# deska.net
KiCad netlist of a schematic drawn in EAGLE
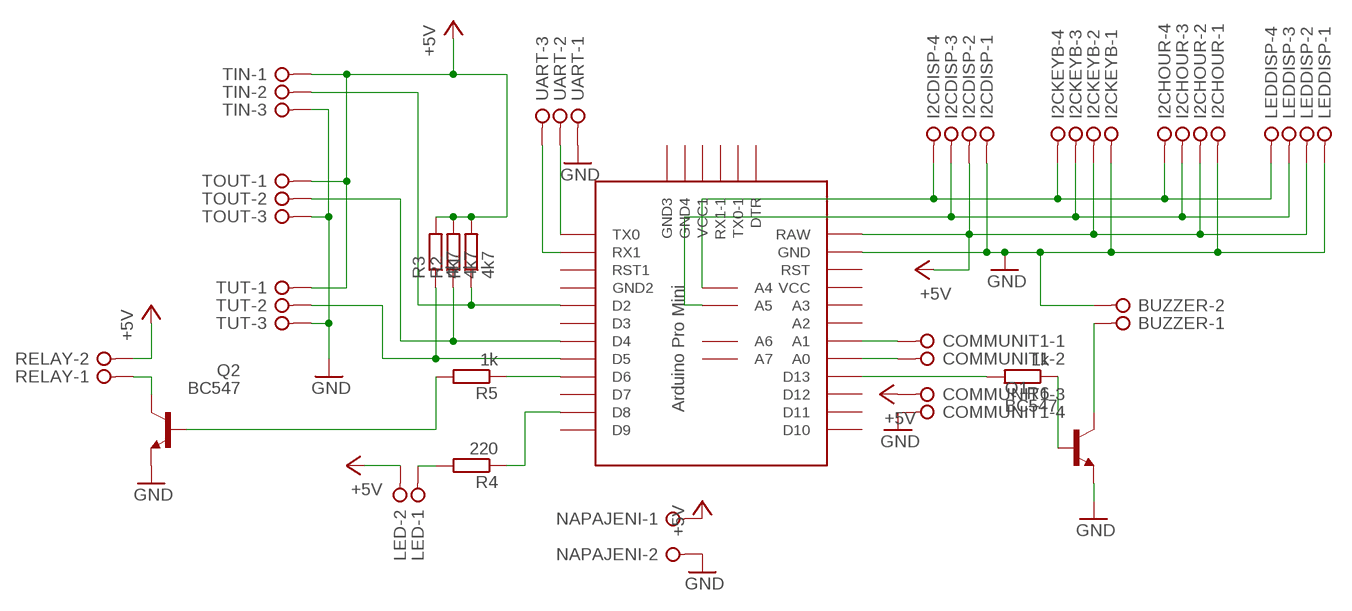
[diagram p0: schematic, sheet 1]

(export (version "E")
  (design (tool "Eeschema 10.0.6"))
  (components
    (comp (ref "BUZZER")
      (value "W237-02P")
      (footprint "eagle-import:W237-132")
      (libsource (lib "eagle-import") (part "W237-02P"))
    )
    (comp (ref "COMMUNIT1")
      (value "W237-04P")
      (footprint "eagle-import:W237-4P")
      (libsource (lib "eagle-import") (part "W237-04P"))
    )
    (comp (ref "I2CDISP")
      (value "W237-04P")
      (footprint "eagle-import:W237-4P")
      (libsource (lib "eagle-import") (part "W237-04P"))
    )
    (comp (ref "I2CHOUR")
      (value "W237-04P")
      (footprint "eagle-import:W237-4P")
      (libsource (lib "eagle-import") (part "W237-04P"))
    )
    (comp (ref "I2CKEYB")
      (value "W237-04P")
      (footprint "eagle-import:W237-4P")
      (libsource (lib "eagle-import") (part "W237-04P"))
    )
    (comp (ref "LED")
      (value "W237-02P")
      (footprint "eagle-import:W237-132")
      (libsource (lib "eagle-import") (part "W237-02P"))
    )
    (comp (ref "LEDDISP")
      (value "W237-04P")
      (footprint "eagle-import:W237-4P")
      (libsource (lib "eagle-import") (part "W237-04P"))
    )
    (comp (ref "NAPAJENI")
      (value "W237-02P")
      (footprint "eagle-import:W237-132")
      (libsource (lib "eagle-import") (part "W237-02P"))
    )
    (comp (ref "Q1")
      (value "BC547")
      (footprint "eagle-import:TO92")
      (libsource (lib "eagle-import") (part "BC547"))
    )
    (comp (ref "Q2")
      (value "BC547")
      (footprint "eagle-import:TO92")
      (libsource (lib "eagle-import") (part "BC547"))
    )
    (comp (ref "R1")
      (value "4k7")
      (footprint "eagle-import:0207_7")
      (libsource (lib "eagle-import") (part "R-EU_0207/7"))
    )
    (comp (ref "R2")
      (value "4k7")
      (footprint "eagle-import:0207_7")
      (libsource (lib "eagle-import") (part "R-EU_0207/7"))
    )
    (comp (ref "R3")
      (value "4k7")
      (footprint "eagle-import:0207_7")
      (libsource (lib "eagle-import") (part "R-EU_0207/7"))
    )
    (comp (ref "R4")
      (value "220")
      (footprint "eagle-import:0207_7")
      (libsource (lib "eagle-import") (part "R-EU_0207/7"))
    )
    (comp (ref "R5")
      (value "1k")
      (footprint "eagle-import:0207_7")
      (libsource (lib "eagle-import") (part "R-EU_0207/7"))
    )
    (comp (ref "R6")
      (value "1k")
      (footprint "eagle-import:0207_7")
      (libsource (lib "eagle-import") (part "R-EU_0207/7"))
    )
    (comp (ref "RELAY")
      (value "W237-02P")
      (footprint "eagle-import:W237-132")
      (libsource (lib "eagle-import") (part "W237-02P"))
    )
    (comp (ref "TIN")
      (value "W237-3E")
      (footprint "eagle-import:W237-3E")
      (libsource (lib "eagle-import") (part "W237-3E"))
    )
    (comp (ref "TOUT")
      (value "W237-3E")
      (footprint "eagle-import:W237-3E")
      (libsource (lib "eagle-import") (part "W237-3E"))
    )
    (comp (ref "TUT")
      (value "W237-3E")
      (footprint "eagle-import:W237-3E")
      (libsource (lib "eagle-import") (part "W237-3E"))
    )
    (comp (ref "U$1")
      (value "PRO-MINI-2")
      (footprint "eagle-import:PRO-MINI-2")
      (libsource (lib "eagle-import") (part "PRO-MINI-2"))
    )
    (comp (ref "UART")
      (value "W237-3E")
      (footprint "eagle-import:W237-3E")
      (libsource (lib "eagle-import") (part "W237-3E"))
    )
  )
  (nets
    (net (code "1") (name "+5V") (class "Default")
      (node (ref "COMMUNIT1") (pin "3") (pinfunction "KL_3") (pintype "passive"))
      (node (ref "I2CDISP") (pin "2") (pinfunction "KL_2") (pintype "passive"))
      (node (ref "I2CHOUR") (pin "2") (pinfunction "KL_2") (pintype "passive"))
      (node (ref "I2CKEYB") (pin "2") (pinfunction "KL_2") (pintype "passive"))
      (node (ref "LED") (pin "2") (pinfunction "KL_2") (pintype "passive"))
      (node (ref "LEDDISP") (pin "2") (pinfunction "KL_2") (pintype "passive"))
      (node (ref "NAPAJENI") (pin "1") (pinfunction "KL_1") (pintype "passive"))
      (node (ref "R1") (pin "2") (pinfunction "2_2") (pintype "passive"))
      (node (ref "R2") (pin "2") (pinfunction "2_2") (pintype "passive"))
      (node (ref "R3") (pin "2") (pinfunction "2_2") (pintype "passive"))
      (node (ref "RELAY") (pin "2") (pinfunction "KL_2") (pintype "passive"))
      (node (ref "TIN") (pin "1") (pinfunction "KL_1") (pintype "passive"))
      (node (ref "TOUT") (pin "1") (pinfunction "KL_1") (pintype "passive"))
      (node (ref "TUT") (pin "1") (pinfunction "KL_1") (pintype "passive"))
      (node (ref "U$1") (pin "RAW") (pinfunction "RAW_RAW") (pintype "bidirectional"))
    )
    (net (code "2") (name "GND") (class "Default")
      (node (ref "BUZZER") (pin "2") (pinfunction "KL_2") (pintype "passive"))
      (node (ref "COMMUNIT1") (pin "4") (pinfunction "KL_4") (pintype "passive"))
      (node (ref "I2CDISP") (pin "1") (pinfunction "KL_1") (pintype "passive"))
      (node (ref "I2CHOUR") (pin "1") (pinfunction "KL_1") (pintype "passive"))
      (node (ref "I2CKEYB") (pin "1") (pinfunction "KL_1") (pintype "passive"))
      (node (ref "LEDDISP") (pin "1") (pinfunction "KL_1") (pintype "passive"))
      (node (ref "NAPAJENI") (pin "2") (pinfunction "KL_2") (pintype "passive"))
      (node (ref "Q1") (pin "1") (pinfunction "E_1") (pintype "passive"))
      (node (ref "Q2") (pin "1") (pinfunction "E_1") (pintype "passive"))
      (node (ref "TIN") (pin "3") (pinfunction "KL_3") (pintype "passive"))
      (node (ref "TOUT") (pin "3") (pinfunction "KL_3") (pintype "passive"))
      (node (ref "TUT") (pin "3") (pinfunction "KL_3") (pintype "passive"))
      (node (ref "U$1") (pin "GND") (pinfunction "GND_GND") (pintype "bidirectional"))
      (node (ref "UART") (pin "1") (pinfunction "KL_1") (pintype "passive"))
    )
    (net (code "3") (name "Net-(BUZZERA-KL)") (class "Default")
      (node (ref "BUZZER") (pin "1") (pinfunction "KL_1") (pintype "passive"))
      (node (ref "Q1") (pin "3") (pinfunction "C_3") (pintype "passive"))
    )
    (net (code "4") (name "Net-(COMMUNIT1A-KL)") (class "Default")
      (node (ref "COMMUNIT1") (pin "1") (pinfunction "KL_1") (pintype "passive"))
      (node (ref "U$1") (pin "A1") (pinfunction "A1_A1") (pintype "bidirectional"))
    )
    (net (code "5") (name "Net-(COMMUNIT1B-KL)") (class "Default")
      (node (ref "COMMUNIT1") (pin "2") (pinfunction "KL_2") (pintype "passive"))
      (node (ref "U$1") (pin "A0") (pinfunction "A0_A0") (pintype "bidirectional"))
    )
    (net (code "6") (name "Net-(I2CDISPC-KL)") (class "Default")
      (node (ref "I2CDISP") (pin "3") (pinfunction "KL_3") (pintype "passive"))
      (node (ref "I2CHOUR") (pin "3") (pinfunction "KL_3") (pintype "passive"))
      (node (ref "I2CKEYB") (pin "3") (pinfunction "KL_3") (pintype "passive"))
      (node (ref "LEDDISP") (pin "3") (pinfunction "KL_3") (pintype "passive"))
      (node (ref "U$1") (pin "A5") (pinfunction "A5_A5") (pintype "bidirectional"))
    )
    (net (code "7") (name "Net-(I2CDISPD-KL)") (class "Default")
      (node (ref "I2CDISP") (pin "4") (pinfunction "KL_4") (pintype "passive"))
      (node (ref "I2CHOUR") (pin "4") (pinfunction "KL_4") (pintype "passive"))
      (node (ref "I2CKEYB") (pin "4") (pinfunction "KL_4") (pintype "passive"))
      (node (ref "LEDDISP") (pin "4") (pinfunction "KL_4") (pintype "passive"))
      (node (ref "U$1") (pin "A4") (pinfunction "A4_A4") (pintype "bidirectional"))
    )
    (net (code "8") (name "Net-(LEDA-KL)") (class "Default")
      (node (ref "LED") (pin "1") (pinfunction "KL_1") (pintype "passive"))
      (node (ref "R4") (pin "2") (pinfunction "2_2") (pintype "passive"))
    )
    (net (code "9") (name "Net-(Q1-B)") (class "Default")
      (node (ref "Q1") (pin "2") (pinfunction "B_2") (pintype "passive"))
      (node (ref "R6") (pin "1") (pinfunction "1_1") (pintype "passive"))
    )
    (net (code "10") (name "Net-(Q2-B)") (class "Default")
      (node (ref "Q2") (pin "2") (pinfunction "B_2") (pintype "passive"))
      (node (ref "R5") (pin "2") (pinfunction "2_2") (pintype "passive"))
    )
    (net (code "11") (name "Net-(Q2-C)") (class "Default")
      (node (ref "Q2") (pin "3") (pinfunction "C_3") (pintype "passive"))
      (node (ref "RELAY") (pin "1") (pinfunction "KL_1") (pintype "passive"))
    )
    (net (code "12") (name "Net-(R4-Pad1)") (class "Default")
      (node (ref "R4") (pin "1") (pinfunction "1_1") (pintype "passive"))
      (node (ref "U$1") (pin "D8") (pinfunction "D8_D8") (pintype "bidirectional"))
    )
    (net (code "13") (name "Net-(R5-Pad1)") (class "Default")
      (node (ref "R5") (pin "1") (pinfunction "1_1") (pintype "passive"))
      (node (ref "U$1") (pin "D6") (pinfunction "D6_D6") (pintype "bidirectional"))
    )
    (net (code "14") (name "Net-(R6-Pad2)") (class "Default")
      (node (ref "R6") (pin "2") (pinfunction "2_2") (pintype "passive"))
      (node (ref "U$1") (pin "D13") (pinfunction "D13_D13") (pintype "bidirectional"))
    )
    (net (code "15") (name "Net-(TINB-KL)") (class "Default")
      (node (ref "R1") (pin "1") (pinfunction "1_1") (pintype "passive"))
      (node (ref "TIN") (pin "2") (pinfunction "KL_2") (pintype "passive"))
      (node (ref "U$1") (pin "D2") (pinfunction "D2_D2") (pintype "bidirectional"))
    )
    (net (code "16") (name "Net-(TOUTB-KL)") (class "Default")
      (node (ref "R2") (pin "1") (pinfunction "1_1") (pintype "passive"))
      (node (ref "TOUT") (pin "2") (pinfunction "KL_2") (pintype "passive"))
      (node (ref "U$1") (pin "D4") (pinfunction "D4_D4") (pintype "bidirectional"))
    )
    (net (code "17") (name "Net-(TUTB-KL)") (class "Default")
      (node (ref "R3") (pin "1") (pinfunction "1_1") (pintype "passive"))
      (node (ref "TUT") (pin "2") (pinfunction "KL_2") (pintype "passive"))
      (node (ref "U$1") (pin "D5") (pinfunction "D5_D5") (pintype "bidirectional"))
    )
    (net (code "18") (name "Net-(UARTB-KL)") (class "Default")
      (node (ref "U$1") (pin "TX0") (pinfunction "TX0_TX0") (pintype "bidirectional"))
      (node (ref "UART") (pin "2") (pinfunction "KL_2") (pintype "passive"))
    )
    (net (code "19") (name "Net-(UARTC-KL)") (class "Default")
      (node (ref "U$1") (pin "RX1") (pinfunction "RX1_RX1") (pintype "bidirectional"))
      (node (ref "UART") (pin "3") (pinfunction "KL_3") (pintype "passive"))
    )
    (net (code "20") (name "unconnected-(U$1-GND2-PadGND1)") (class "Default")
      (node (ref "U$1") (pin "GND1") (pinfunction "GND2_GND1") (pintype "bidirectional"))
    )
    (net (code "21") (name "unconnected-(U$1-GND3-PadGND2)") (class "Default")
      (node (ref "U$1") (pin "GND2") (pinfunction "GND3_GND2") (pintype "bidirectional"))
    )
    (net (code "22") (name "unconnected-(U$1-GND4-PadGND3)") (class "Default")
      (node (ref "U$1") (pin "GND3") (pinfunction "GND4_GND3") (pintype "bidirectional"))
    )
    (net (code "23") (name "unconnected-(U$1-PadA2)") (class "Default")
      (node (ref "U$1") (pin "A2") (pinfunction "A2_A2") (pintype "bidirectional"))
    )
    (net (code "24") (name "unconnected-(U$1-PadA3)") (class "Default")
      (node (ref "U$1") (pin "A3") (pinfunction "A3_A3") (pintype "bidirectional"))
    )
    (net (code "25") (name "unconnected-(U$1-PadA6)") (class "Default")
      (node (ref "U$1") (pin "A6") (pinfunction "A6_A6") (pintype "bidirectional"))
    )
    (net (code "26") (name "unconnected-(U$1-PadA7)") (class "Default")
      (node (ref "U$1") (pin "A7") (pinfunction "A7_A7") (pintype "bidirectional"))
    )
    (net (code "27") (name "unconnected-(U$1-PadD3)") (class "Default")
      (node (ref "U$1") (pin "D3") (pinfunction "D3_D3") (pintype "bidirectional"))
    )
    (net (code "28") (name "unconnected-(U$1-PadD7)") (class "Default")
      (node (ref "U$1") (pin "D7") (pinfunction "D7_D7") (pintype "bidirectional"))
    )
    (net (code "29") (name "unconnected-(U$1-PadD9)") (class "Default")
      (node (ref "U$1") (pin "D9") (pinfunction "D9_D9") (pintype "bidirectional"))
    )
    (net (code "30") (name "unconnected-(U$1-PadD10)") (class "Default")
      (node (ref "U$1") (pin "D10") (pinfunction "D10_D10") (pintype "bidirectional"))
    )
    (net (code "31") (name "unconnected-(U$1-PadD11)") (class "Default")
      (node (ref "U$1") (pin "D11") (pinfunction "D11_D11") (pintype "bidirectional"))
    )
    (net (code "32") (name "unconnected-(U$1-PadD12)") (class "Default")
      (node (ref "U$1") (pin "D12") (pinfunction "D12_D12") (pintype "bidirectional"))
    )
    (net (code "33") (name "unconnected-(U$1-PadDTR)") (class "Default")
      (node (ref "U$1") (pin "DTR") (pinfunction "DTR_DTR") (pintype "bidirectional"))
    )
    (net (code "34") (name "unconnected-(U$1-PadRST)") (class "Default")
      (node (ref "U$1") (pin "RST") (pinfunction "RST_RST") (pintype "bidirectional"))
    )
    (net (code "35") (name "unconnected-(U$1-PadRST1)") (class "Default")
      (node (ref "U$1") (pin "RST1") (pinfunction "RST1_RST1") (pintype "bidirectional"))
    )
    (net (code "36") (name "unconnected-(U$1-PadRX1-1)") (class "Default")
      (node (ref "U$1") (pin "RX1-1") (pinfunction "RX1-1_RX1-1") (pintype "bidirectional"))
    )
    (net (code "37") (name "unconnected-(U$1-PadTX0-1)") (class "Default")
      (node (ref "U$1") (pin "TX0-1") (pinfunction "TX0-1_TX0-1") (pintype "bidirectional"))
    )
    (net (code "38") (name "unconnected-(U$1-PadVCC)") (class "Default")
      (node (ref "U$1") (pin "VCC") (pinfunction "VCC_VCC") (pintype "bidirectional"))
    )
    (net (code "39") (name "unconnected-(U$1-PadVCC1)") (class "Default")
      (node (ref "U$1") (pin "VCC1") (pinfunction "VCC1_VCC1") (pintype "bidirectional"))
    )
  )
)
